# Sheet1.net
KiCad netlist of a schematic drawn in Altium Designer
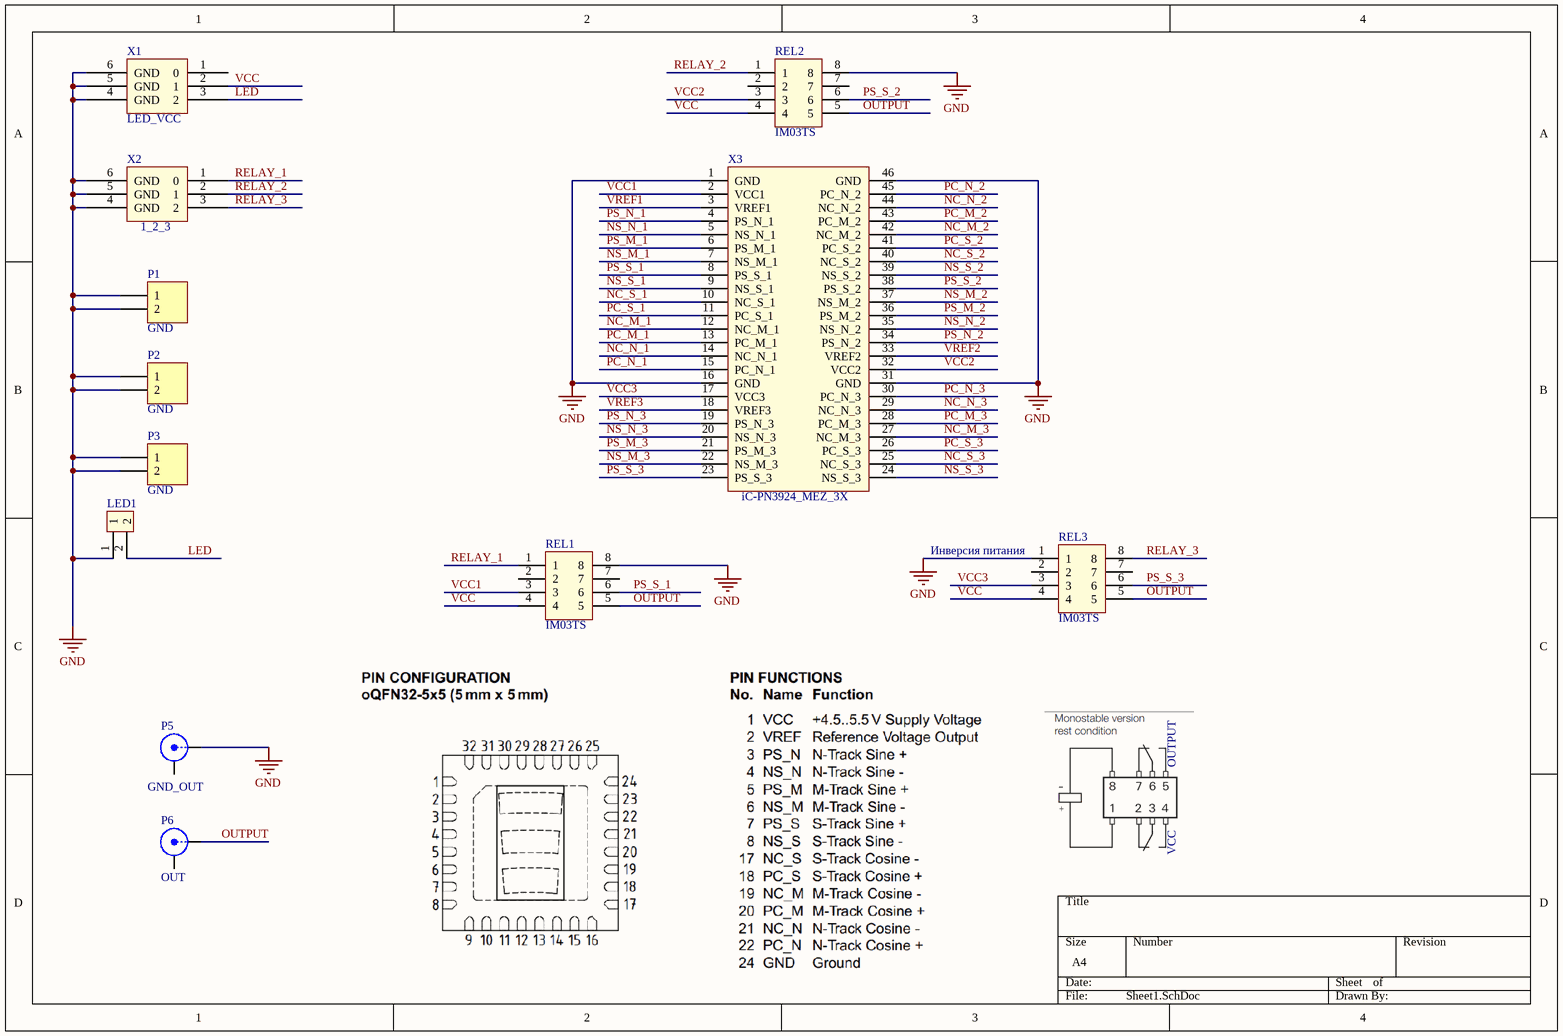
[diagram p0: Sheet1.SchDoc]

(export (version "E")
  (design (tool "Eeschema 10.0.6"))
  (components
    (comp (ref "LED1") (value "KL_2") (footprint "KLEMMNIK_2") (libsource (lib "Schlib") (part "KLEMMNIK_2")))
    (comp (ref "P1")
      (value "GND")
      (footprint "HDR1X2")
      (description "Header, 2-Pin")
      (fields (field (name "PUBLISHER") "Altium Limited"))
      (libsource (lib "Miscellaneous Connectors") (part "Header 2"))
    )
    (comp (ref "P2")
      (value "GND")
      (footprint "HDR1X2")
      (description "Header, 2-Pin")
      (fields (field (name "PUBLISHER") "Altium Limited"))
      (libsource (lib "Miscellaneous Connectors") (part "Header 2"))
    )
    (comp (ref "P3")
      (value "GND")
      (footprint "HDR1X2")
      (description "Header, 2-Pin")
      (fields (field (name "PUBLISHER") "Altium Limited"))
      (libsource (lib "Miscellaneous Connectors") (part "Header 2"))
    )
    (comp (ref "P5")
      (value "GND_OUT")
      (footprint "BNC_RA CON")
      (description "BNC Elbow Connector")
      (fields (field (name "PUBLISHER") "Altium Limited"))
      (libsource (lib "Miscellaneous Connectors") (part "BNC"))
    )
    (comp (ref "P6")
      (value "OUT")
      (footprint "BNC_RA CON")
      (description "BNC Elbow Connector")
      (fields (field (name "PUBLISHER") "Altium Limited"))
      (libsource (lib "Miscellaneous Connectors") (part "BNC"))
    )
    (comp (ref "REL1") (value "IM03TS") (footprint "IM03TS") (libsource (lib "Schlib") (part "IM03TS")))
    (comp (ref "REL2") (value "IM03TS") (footprint "IM03TS") (libsource (lib "Schlib") (part "IM03TS")))
    (comp (ref "REL3") (value "IM03TS") (footprint "IM03TS") (libsource (lib "Schlib") (part "IM03TS")))
    (comp (ref "X1") (value "LED_VCC") (footprint "POWER") (libsource (lib "Schlib") (part "POWER")))
    (comp (ref "X2") (value "1_2_3") (footprint "POWER") (libsource (lib "Schlib") (part "POWER")))
    (comp (ref "X3")
      (value "iC-PN3924_MEZ_3X")
      (footprint "iC-PN3924_MEZ_3X")
      (libsource (lib "Schlib") (part "iC-PN3924_MEZ_3X"))
    )
  )
  (nets
    (net (code "1") (name "/LED") (class "Default")
      (node (ref "LED1") (pin "2") (pinfunction "2_2") (pintype "passive"))
      (node (ref "X1") (pin "3") (pinfunction "2_3") (pintype "passive"))
    )
    (net (code "2") (name "/NC_M_1") (class "Default")
      (node (ref "X3") (pin "12") (pinfunction "NC_M_1_12") (pintype "passive"))
    )
    (net (code "3") (name "/NC_M_2") (class "Default")
      (node (ref "X3") (pin "42") (pinfunction "NC_M_2_42") (pintype "passive"))
    )
    (net (code "4") (name "/NC_M_3") (class "Default")
      (node (ref "X3") (pin "27") (pinfunction "NC_M_3_27") (pintype "passive"))
    )
    (net (code "5") (name "/NC_N_1") (class "Default")
      (node (ref "X3") (pin "14") (pinfunction "NC_N_1_14") (pintype "passive"))
    )
    (net (code "6") (name "/NC_N_2") (class "Default")
      (node (ref "X3") (pin "44") (pinfunction "NC_N_2_44") (pintype "passive"))
    )
    (net (code "7") (name "/NC_N_3") (class "Default")
      (node (ref "X3") (pin "29") (pinfunction "NC_N_3_29") (pintype "passive"))
    )
    (net (code "8") (name "/NC_S_1") (class "Default")
      (node (ref "X3") (pin "10") (pinfunction "NC_S_1_10") (pintype "passive"))
    )
    (net (code "9") (name "/NC_S_2") (class "Default")
      (node (ref "X3") (pin "40") (pinfunction "NC_S_2_40") (pintype "passive"))
    )
    (net (code "10") (name "/NC_S_3") (class "Default")
      (node (ref "X3") (pin "25") (pinfunction "NC_S_3_25") (pintype "passive"))
    )
    (net (code "11") (name "/NS_M_1") (class "Default")
      (node (ref "X3") (pin "7") (pinfunction "NS_M_1_7") (pintype "passive"))
    )
    (net (code "12") (name "/NS_M_2") (class "Default")
      (node (ref "X3") (pin "37") (pinfunction "NS_M_2_37") (pintype "passive"))
    )
    (net (code "13") (name "/NS_M_3") (class "Default")
      (node (ref "X3") (pin "22") (pinfunction "NS_M_3_22") (pintype "passive"))
    )
    (net (code "14") (name "/NS_N_1") (class "Default")
      (node (ref "X3") (pin "5") (pinfunction "NS_N_1_5") (pintype "passive"))
    )
    (net (code "15") (name "/NS_N_2") (class "Default")
      (node (ref "X3") (pin "35") (pinfunction "NS_N_2_35") (pintype "passive"))
    )
    (net (code "16") (name "/NS_N_3") (class "Default")
      (node (ref "X3") (pin "20") (pinfunction "NS_N_3_20") (pintype "passive"))
    )
    (net (code "17") (name "/NS_S_1") (class "Default")
      (node (ref "X3") (pin "9") (pinfunction "NS_S_1_9") (pintype "passive"))
    )
    (net (code "18") (name "/NS_S_2") (class "Default")
      (node (ref "X3") (pin "39") (pinfunction "NS_S_2_39") (pintype "passive"))
    )
    (net (code "19") (name "/NS_S_3") (class "Default")
      (node (ref "X3") (pin "24") (pinfunction "NS_S_3_24") (pintype "passive"))
    )
    (net (code "20") (name "/OUTPUT") (class "Default")
      (node (ref "P6") (pin "1") (pinfunction "X_1") (pintype "passive"))
      (node (ref "REL1") (pin "5") (pinfunction "5_5") (pintype "passive"))
      (node (ref "REL2") (pin "5") (pinfunction "5_5") (pintype "passive"))
      (node (ref "REL3") (pin "5") (pinfunction "5_5") (pintype "passive"))
    )
    (net (code "21") (name "/PC_M_1") (class "Default")
      (node (ref "X3") (pin "13") (pinfunction "PC_M_1_13") (pintype "passive"))
    )
    (net (code "22") (name "/PC_M_2") (class "Default")
      (node (ref "X3") (pin "43") (pinfunction "PC_M_2_43") (pintype "passive"))
    )
    (net (code "23") (name "/PC_M_3") (class "Default")
      (node (ref "X3") (pin "28") (pinfunction "PC_M_3_28") (pintype "passive"))
    )
    (net (code "24") (name "/PC_N_1") (class "Default")
      (node (ref "X3") (pin "15") (pinfunction "PC_N_1_15") (pintype "passive"))
    )
    (net (code "25") (name "/PC_N_2") (class "Default")
      (node (ref "X3") (pin "45") (pinfunction "PC_N_2_45") (pintype "passive"))
    )
    (net (code "26") (name "/PC_N_3") (class "Default")
      (node (ref "X3") (pin "30") (pinfunction "PC_N_3_30") (pintype "passive"))
    )
    (net (code "27") (name "/PC_S_1") (class "Default")
      (node (ref "X3") (pin "11") (pinfunction "PC_S_1_11") (pintype "passive"))
    )
    (net (code "28") (name "/PC_S_2") (class "Default")
      (node (ref "X3") (pin "41") (pinfunction "PC_S_2_41") (pintype "passive"))
    )
    (net (code "29") (name "/PC_S_3") (class "Default")
      (node (ref "X3") (pin "26") (pinfunction "PC_S_3_26") (pintype "passive"))
    )
    (net (code "30") (name "/PS_M_1") (class "Default")
      (node (ref "X3") (pin "6") (pinfunction "PS_M_1_6") (pintype "passive"))
    )
    (net (code "31") (name "/PS_M_2") (class "Default")
      (node (ref "X3") (pin "36") (pinfunction "PS_M_2_36") (pintype "passive"))
    )
    (net (code "32") (name "/PS_M_3") (class "Default")
      (node (ref "X3") (pin "21") (pinfunction "PS_M_3_21") (pintype "passive"))
    )
    (net (code "33") (name "/PS_N_1") (class "Default")
      (node (ref "X3") (pin "4") (pinfunction "PS_N_1_4") (pintype "passive"))
    )
    (net (code "34") (name "/PS_N_2") (class "Default")
      (node (ref "X3") (pin "34") (pinfunction "PS_N_2_34") (pintype "passive"))
    )
    (net (code "35") (name "/PS_N_3") (class "Default")
      (node (ref "X3") (pin "19") (pinfunction "PS_N_3_19") (pintype "passive"))
    )
    (net (code "36") (name "/PS_S_1") (class "Default")
      (node (ref "REL1") (pin "6") (pinfunction "6_6") (pintype "passive"))
      (node (ref "X3") (pin "8") (pinfunction "PS_S_1_8") (pintype "passive"))
    )
    (net (code "37") (name "/PS_S_2") (class "Default")
      (node (ref "REL2") (pin "6") (pinfunction "6_6") (pintype "passive"))
      (node (ref "X3") (pin "38") (pinfunction "PS_S_2_38") (pintype "passive"))
    )
    (net (code "38") (name "/PS_S_3") (class "Default")
      (node (ref "REL3") (pin "6") (pinfunction "6_6") (pintype "passive"))
      (node (ref "X3") (pin "23") (pinfunction "PS_S_3_23") (pintype "passive"))
    )
    (net (code "39") (name "/RELAY_1") (class "Default")
      (node (ref "REL1") (pin "1") (pinfunction "1_1") (pintype "passive"))
      (node (ref "X2") (pin "1") (pinfunction "0_1") (pintype "passive"))
    )
    (net (code "40") (name "/RELAY_2") (class "Default")
      (node (ref "REL2") (pin "1") (pinfunction "1_1") (pintype "passive"))
      (node (ref "X2") (pin "2") (pinfunction "1_2") (pintype "passive"))
    )
    (net (code "41") (name "/RELAY_3") (class "Default")
      (node (ref "REL3") (pin "8") (pinfunction "8_8") (pintype "passive"))
      (node (ref "X2") (pin "3") (pinfunction "2_3") (pintype "passive"))
    )
    (net (code "42") (name "/VCC") (class "Default")
      (node (ref "REL1") (pin "4") (pinfunction "4_4") (pintype "passive"))
      (node (ref "REL2") (pin "4") (pinfunction "4_4") (pintype "passive"))
      (node (ref "REL3") (pin "4") (pinfunction "4_4") (pintype "passive"))
      (node (ref "X1") (pin "2") (pinfunction "1_2") (pintype "passive"))
    )
    (net (code "43") (name "/VCC1") (class "Default")
      (node (ref "REL1") (pin "3") (pinfunction "3_3") (pintype "passive"))
      (node (ref "X3") (pin "2") (pinfunction "VCC1_2") (pintype "passive"))
    )
    (net (code "44") (name "/VCC2") (class "Default")
      (node (ref "REL2") (pin "3") (pinfunction "3_3") (pintype "passive"))
      (node (ref "X3") (pin "32") (pinfunction "VCC2_32") (pintype "passive"))
    )
    (net (code "45") (name "/VCC3") (class "Default")
      (node (ref "REL3") (pin "3") (pinfunction "3_3") (pintype "passive"))
      (node (ref "X3") (pin "17") (pinfunction "VCC3_17") (pintype "passive"))
    )
    (net (code "46") (name "/VREF1") (class "Default")
      (node (ref "X3") (pin "3") (pinfunction "VREF1_3") (pintype "passive"))
    )
    (net (code "47") (name "/VREF2") (class "Default")
      (node (ref "X3") (pin "33") (pinfunction "VREF2_33") (pintype "passive"))
    )
    (net (code "48") (name "/VREF3") (class "Default")
      (node (ref "X3") (pin "18") (pinfunction "VREF3_18") (pintype "passive"))
    )
    (net (code "49") (name "GND") (class "Default")
      (node (ref "LED1") (pin "1") (pinfunction "1_1") (pintype "passive"))
      (node (ref "P1") (pin "1") (pinfunction "1_1") (pintype "passive"))
      (node (ref "P1") (pin "2") (pinfunction "2_2") (pintype "passive"))
      (node (ref "P2") (pin "1") (pinfunction "1_1") (pintype "passive"))
      (node (ref "P2") (pin "2") (pinfunction "2_2") (pintype "passive"))
      (node (ref "P3") (pin "1") (pinfunction "1_1") (pintype "passive"))
      (node (ref "P3") (pin "2") (pinfunction "2_2") (pintype "passive"))
      (node (ref "P5") (pin "1") (pinfunction "X_1") (pintype "passive"))
      (node (ref "REL1") (pin "8") (pinfunction "8_8") (pintype "passive"))
      (node (ref "REL2") (pin "8") (pinfunction "8_8") (pintype "passive"))
      (node (ref "REL3") (pin "1") (pinfunction "1_1") (pintype "passive"))
      (node (ref "X1") (pin "4") (pinfunction "GND_4") (pintype "passive"))
      (node (ref "X1") (pin "5") (pinfunction "GND_5") (pintype "passive"))
      (node (ref "X1") (pin "6") (pinfunction "GND_6") (pintype "passive"))
      (node (ref "X2") (pin "4") (pinfunction "GND_4") (pintype "passive"))
      (node (ref "X2") (pin "5") (pinfunction "GND_5") (pintype "passive"))
      (node (ref "X2") (pin "6") (pinfunction "GND_6") (pintype "passive"))
      (node (ref "X3") (pin "1") (pinfunction "GND_1") (pintype "passive"))
      (node (ref "X3") (pin "16") (pinfunction "GND_16") (pintype "passive"))
      (node (ref "X3") (pin "31") (pinfunction "GND_31") (pintype "passive"))
      (node (ref "X3") (pin "46") (pinfunction "GND_46") (pintype "passive"))
    )
    (net (code "50") (name "unconnected-(P5-Y-Pad2)") (class "Default")
      (node (ref "P5") (pin "2") (pinfunction "Y_2") (pintype "passive"))
    )
    (net (code "51") (name "unconnected-(P6-Y-Pad2)") (class "Default")
      (node (ref "P6") (pin "2") (pinfunction "Y_2") (pintype "passive"))
    )
    (net (code "52") (name "unconnected-(REL1-Pad2)") (class "Default")
      (node (ref "REL1") (pin "2") (pinfunction "2_2") (pintype "passive"))
    )
    (net (code "53") (name "unconnected-(REL1-Pad7)") (class "Default")
      (node (ref "REL1") (pin "7") (pinfunction "7_7") (pintype "passive"))
    )
    (net (code "54") (name "unconnected-(REL2-Pad2)") (class "Default")
      (node (ref "REL2") (pin "2") (pinfunction "2_2") (pintype "passive"))
    )
    (net (code "55") (name "unconnected-(REL2-Pad7)") (class "Default")
      (node (ref "REL2") (pin "7") (pinfunction "7_7") (pintype "passive"))
    )
    (net (code "56") (name "unconnected-(REL3-Pad2)") (class "Default")
      (node (ref "REL3") (pin "2") (pinfunction "2_2") (pintype "passive"))
    )
    (net (code "57") (name "unconnected-(REL3-Pad7)") (class "Default")
      (node (ref "REL3") (pin "7") (pinfunction "7_7") (pintype "passive"))
    )
    (net (code "58") (name "unconnected-(X1-0-Pad1)") (class "Default")
      (node (ref "X1") (pin "1") (pinfunction "0_1") (pintype "passive"))
    )
  )
)
